# Peripheral.net
KiCad netlist of a schematic drawn in Altium Designer
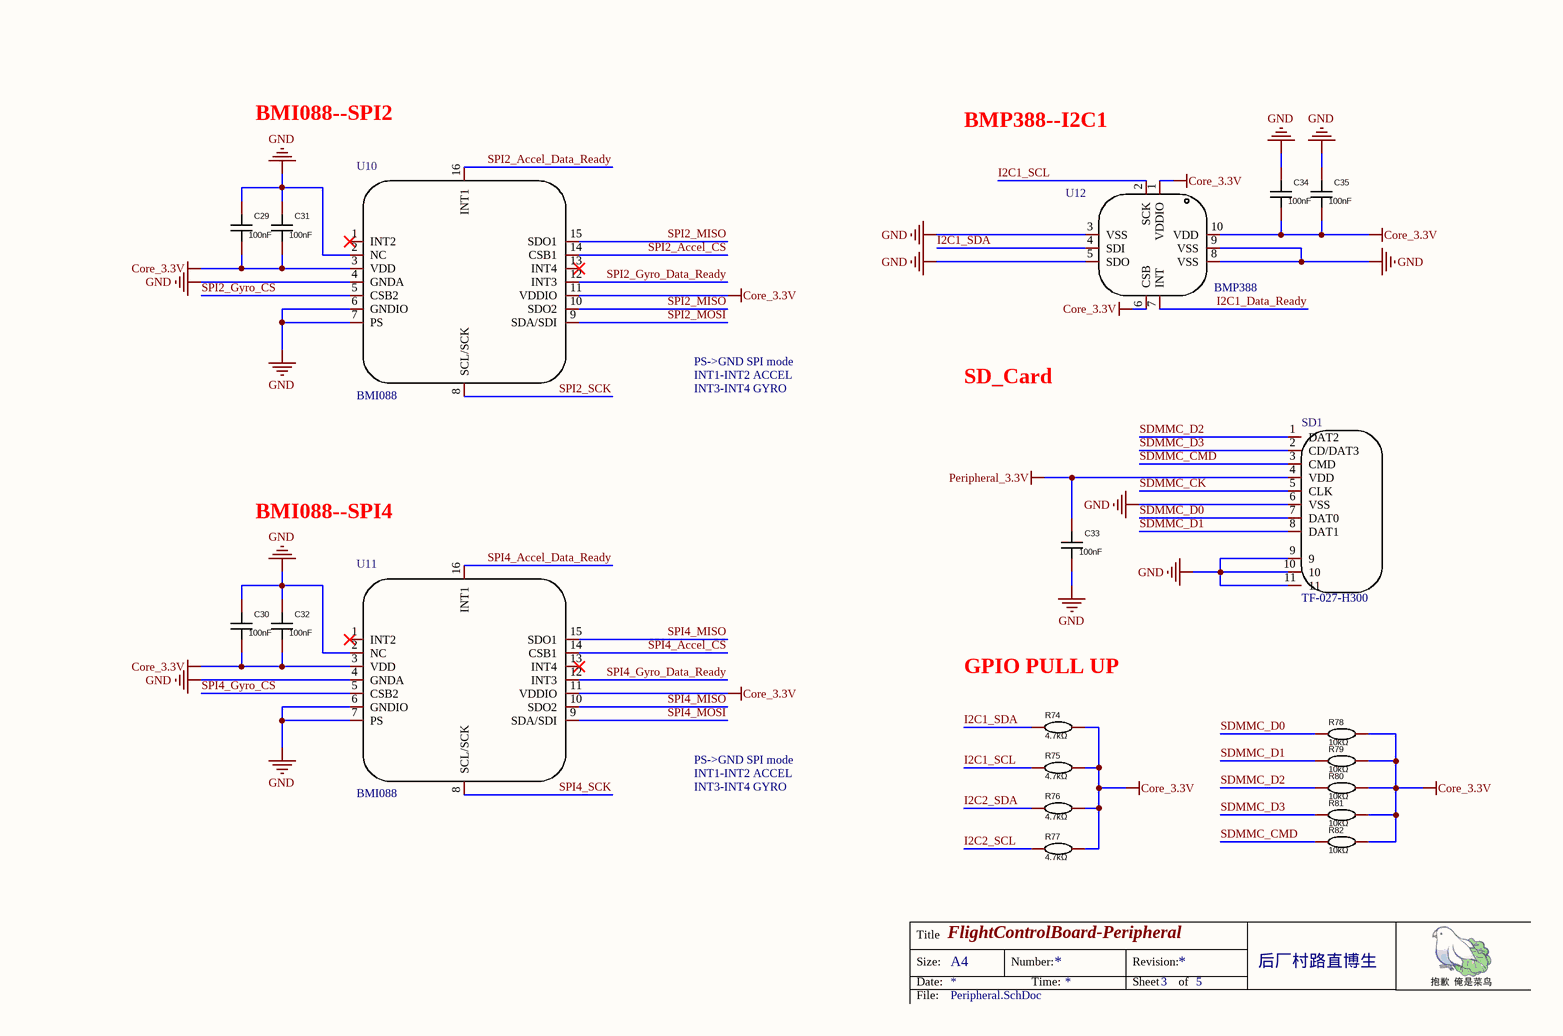
[diagram p0: Peripheral.SchDoc]

(export (version "E")
  (design (tool "Eeschema 10.0.6"))
  (components
    (comp (ref "C29")
      (value "100nF")
      (footprint "C0201")
      (libsource (lib "Capacitor") (part "CC0603KRX7R9BB104"))
    )
    (comp (ref "C30")
      (value "100nF")
      (footprint "C0201")
      (libsource (lib "Capacitor") (part "CC0603KRX7R9BB104"))
    )
    (comp (ref "C31")
      (value "100nF")
      (footprint "C0201")
      (libsource (lib "Capacitor") (part "CC0603KRX7R9BB104"))
    )
    (comp (ref "C32")
      (value "100nF")
      (footprint "C0201")
      (libsource (lib "Capacitor") (part "CC0603KRX7R9BB104"))
    )
    (comp (ref "C33")
      (value "100nF")
      (footprint "C0201")
      (libsource (lib "Capacitor") (part "CC0603KRX7R9BB104"))
    )
    (comp (ref "C34")
      (value "100nF")
      (footprint "C0201")
      (libsource (lib "Capacitor") (part "CC0603KRX7R9BB104"))
    )
    (comp (ref "C35")
      (value "100nF")
      (footprint "C0201")
      (libsource (lib "Capacitor") (part "CC0603KRX7R9BB104"))
    )
    (comp (ref "R74")
      (value "4.7kΩ")
      (footprint "R0201")
      (libsource (lib "Resistor") (part "0603WAF1002T5E"))
    )
    (comp (ref "R75")
      (value "4.7kΩ")
      (footprint "R0201")
      (libsource (lib "Resistor") (part "0603WAF1002T5E"))
    )
    (comp (ref "R76")
      (value "4.7kΩ")
      (footprint "R0201")
      (libsource (lib "Resistor") (part "0603WAF1002T5E"))
    )
    (comp (ref "R77")
      (value "4.7kΩ")
      (footprint "R0201")
      (libsource (lib "Resistor") (part "0603WAF1002T5E"))
    )
    (comp (ref "R78") (value "10kΩ") (footprint "R0201") (libsource (lib "Resistor") (part "0603WAF1002T5E")))
    (comp (ref "R79") (value "10kΩ") (footprint "R0201") (libsource (lib "Resistor") (part "0603WAF1002T5E")))
    (comp (ref "R80") (value "10kΩ") (footprint "R0201") (libsource (lib "Resistor") (part "0603WAF1002T5E")))
    (comp (ref "R81") (value "10kΩ") (footprint "R0201") (libsource (lib "Resistor") (part "0603WAF1002T5E")))
    (comp (ref "R82") (value "10kΩ") (footprint "R0201") (libsource (lib "Resistor") (part "0603WAF1002T5E")))
    (comp (ref "SD1")
      (value "TF-027-H300")
      (footprint "TF-SMD_HYCW104-TF08-375B")
      (fields (field (name "MANUFACTURER") "HANBO(汉博)"))
      (libsource (lib "SD-Card") (part "TF-027-H300"))
    )
    (comp (ref "U10")
      (value "BMI088")
      (footprint "LGA-16_L4.5-W3.0-P0.50-BL")
      (fields (field (name "MANUFACTURER") "Bosch(博世)"))
      (libsource (lib "IMU") (part "BMI088"))
    )
    (comp (ref "U11")
      (value "BMI088")
      (footprint "LGA-16_L4.5-W3.0-P0.50-BL")
      (fields (field (name "MANUFACTURER") "Bosch(博世)"))
      (libsource (lib "IMU") (part "BMI088"))
    )
    (comp (ref "U12")
      (value "BMP388")
      (footprint "LGA-10")
      (fields (field (name "MANUFACTURER") "Bosch(博世)"))
      (libsource (lib "Barometer") (part "BMP388"))
    )
  )
  (nets
    (net (code "1") (name "/I2C1_Data_Ready") (class "Default")
      (node (ref "U12") (pin "7") (pinfunction "INT_7") (pintype "passive"))
    )
    (net (code "2") (name "/I2C1_SCL") (class "Default")
      (node (ref "R75") (pin "1") (pinfunction "1_1") (pintype "passive"))
      (node (ref "U12") (pin "2") (pinfunction "SCK_2") (pintype "passive"))
    )
    (net (code "3") (name "/I2C1_SDA") (class "Default")
      (node (ref "R74") (pin "1") (pinfunction "1_1") (pintype "passive"))
      (node (ref "U12") (pin "4") (pinfunction "SDI_4") (pintype "passive"))
    )
    (net (code "4") (name "/I2C2_SCL") (class "Default")
      (node (ref "R77") (pin "1") (pinfunction "1_1") (pintype "passive"))
    )
    (net (code "5") (name "/I2C2_SDA") (class "Default")
      (node (ref "R76") (pin "1") (pinfunction "1_1") (pintype "passive"))
    )
    (net (code "6") (name "/SDMMC_CK") (class "Default")
      (node (ref "SD1") (pin "5") (pinfunction "CLK_5") (pintype "passive"))
    )
    (net (code "7") (name "/SDMMC_CMD") (class "Default")
      (node (ref "R82") (pin "1") (pinfunction "1_1") (pintype "passive"))
      (node (ref "SD1") (pin "3") (pinfunction "CMD_3") (pintype "passive"))
    )
    (net (code "8") (name "/SDMMC_D0") (class "Default")
      (node (ref "R78") (pin "1") (pinfunction "1_1") (pintype "passive"))
      (node (ref "SD1") (pin "7") (pinfunction "DAT0_7") (pintype "passive"))
    )
    (net (code "9") (name "/SDMMC_D1") (class "Default")
      (node (ref "R79") (pin "1") (pinfunction "1_1") (pintype "passive"))
      (node (ref "SD1") (pin "8") (pinfunction "DAT1_8") (pintype "passive"))
    )
    (net (code "10") (name "/SDMMC_D2") (class "Default")
      (node (ref "R80") (pin "1") (pinfunction "1_1") (pintype "passive"))
      (node (ref "SD1") (pin "1") (pinfunction "DAT2_1") (pintype "passive"))
    )
    (net (code "11") (name "/SDMMC_D3") (class "Default")
      (node (ref "R81") (pin "1") (pinfunction "1_1") (pintype "passive"))
      (node (ref "SD1") (pin "2") (pinfunction "CD/DAT3_2") (pintype "passive"))
    )
    (net (code "12") (name "/SPI2_Accel_CS") (class "Default")
      (node (ref "U10") (pin "14") (pinfunction "CSB1_14") (pintype "passive"))
    )
    (net (code "13") (name "/SPI2_Accel_Data_Ready") (class "Default")
      (node (ref "U10") (pin "16") (pinfunction "INT1_16") (pintype "passive"))
    )
    (net (code "14") (name "/SPI2_Gyro_CS") (class "Default")
      (node (ref "U10") (pin "5") (pinfunction "CSB2_5") (pintype "passive"))
    )
    (net (code "15") (name "/SPI2_Gyro_Data_Ready") (class "Default")
      (node (ref "U10") (pin "12") (pinfunction "INT3_12") (pintype "passive"))
    )
    (net (code "16") (name "/SPI2_MISO") (class "Default")
      (node (ref "U10") (pin "10") (pinfunction "SDO2_10") (pintype "passive"))
      (node (ref "U10") (pin "15") (pinfunction "SDO1_15") (pintype "passive"))
    )
    (net (code "17") (name "/SPI2_MOSI") (class "Default")
      (node (ref "U10") (pin "9") (pinfunction "SDA/SDI_9") (pintype "passive"))
    )
    (net (code "18") (name "/SPI2_SCK") (class "Default")
      (node (ref "U10") (pin "8") (pinfunction "SCL/SCK_8") (pintype "passive"))
    )
    (net (code "19") (name "/SPI4_Accel_CS") (class "Default")
      (node (ref "U11") (pin "14") (pinfunction "CSB1_14") (pintype "passive"))
    )
    (net (code "20") (name "/SPI4_Accel_Data_Ready") (class "Default")
      (node (ref "U11") (pin "16") (pinfunction "INT1_16") (pintype "passive"))
    )
    (net (code "21") (name "/SPI4_Gyro_CS") (class "Default")
      (node (ref "U11") (pin "5") (pinfunction "CSB2_5") (pintype "passive"))
    )
    (net (code "22") (name "/SPI4_Gyro_Data_Ready") (class "Default")
      (node (ref "U11") (pin "12") (pinfunction "INT3_12") (pintype "passive"))
    )
    (net (code "23") (name "/SPI4_MISO") (class "Default")
      (node (ref "U11") (pin "10") (pinfunction "SDO2_10") (pintype "passive"))
      (node (ref "U11") (pin "15") (pinfunction "SDO1_15") (pintype "passive"))
    )
    (net (code "24") (name "/SPI4_MOSI") (class "Default")
      (node (ref "U11") (pin "9") (pinfunction "SDA/SDI_9") (pintype "passive"))
    )
    (net (code "25") (name "/SPI4_SCK") (class "Default")
      (node (ref "U11") (pin "8") (pinfunction "SCL/SCK_8") (pintype "passive"))
    )
    (net (code "26") (name "Core_3.3V") (class "Default")
      (node (ref "C29") (pin "1") (pinfunction "1_1") (pintype "passive"))
      (node (ref "C30") (pin "1") (pinfunction "1_1") (pintype "passive"))
      (node (ref "C31") (pin "1") (pinfunction "1_1") (pintype "passive"))
      (node (ref "C32") (pin "1") (pinfunction "1_1") (pintype "passive"))
      (node (ref "C34") (pin "1") (pinfunction "1_1") (pintype "passive"))
      (node (ref "C35") (pin "1") (pinfunction "1_1") (pintype "passive"))
      (node (ref "R74") (pin "2") (pinfunction "2_2") (pintype "passive"))
      (node (ref "R75") (pin "2") (pinfunction "2_2") (pintype "passive"))
      (node (ref "R76") (pin "2") (pinfunction "2_2") (pintype "passive"))
      (node (ref "R77") (pin "2") (pinfunction "2_2") (pintype "passive"))
      (node (ref "R78") (pin "2") (pinfunction "2_2") (pintype "passive"))
      (node (ref "R79") (pin "2") (pinfunction "2_2") (pintype "passive"))
      (node (ref "R80") (pin "2") (pinfunction "2_2") (pintype "passive"))
      (node (ref "R81") (pin "2") (pinfunction "2_2") (pintype "passive"))
      (node (ref "R82") (pin "2") (pinfunction "2_2") (pintype "passive"))
      (node (ref "U10") (pin "11") (pinfunction "VDDIO_11") (pintype "passive"))
      (node (ref "U10") (pin "3") (pinfunction "VDD_3") (pintype "passive"))
      (node (ref "U11") (pin "11") (pinfunction "VDDIO_11") (pintype "passive"))
      (node (ref "U11") (pin "3") (pinfunction "VDD_3") (pintype "passive"))
      (node (ref "U12") (pin "1") (pinfunction "VDDIO_1") (pintype "passive"))
      (node (ref "U12") (pin "10") (pinfunction "VDD_10") (pintype "passive"))
      (node (ref "U12") (pin "6") (pinfunction "CSB_6") (pintype "passive"))
    )
    (net (code "27") (name "GND") (class "Default")
      (node (ref "C29") (pin "2") (pinfunction "2_2") (pintype "passive"))
      (node (ref "C30") (pin "2") (pinfunction "2_2") (pintype "passive"))
      (node (ref "C31") (pin "2") (pinfunction "2_2") (pintype "passive"))
      (node (ref "C32") (pin "2") (pinfunction "2_2") (pintype "passive"))
      (node (ref "C33") (pin "1") (pinfunction "1_1") (pintype "passive"))
      (node (ref "C34") (pin "2") (pinfunction "2_2") (pintype "passive"))
      (node (ref "C35") (pin "2") (pinfunction "2_2") (pintype "passive"))
      (node (ref "SD1") (pin "10") (pinfunction "10_10") (pintype "passive"))
      (node (ref "SD1") (pin "11") (pinfunction "11_11") (pintype "passive"))
      (node (ref "SD1") (pin "6") (pinfunction "VSS_6") (pintype "passive"))
      (node (ref "SD1") (pin "9") (pinfunction "9_9") (pintype "passive"))
      (node (ref "U10") (pin "2") (pinfunction "NC_2") (pintype "passive"))
      (node (ref "U10") (pin "4") (pinfunction "GNDA_4") (pintype "passive"))
      (node (ref "U10") (pin "6") (pinfunction "GNDIO_6") (pintype "passive"))
      (node (ref "U10") (pin "7") (pinfunction "PS_7") (pintype "passive"))
      (node (ref "U11") (pin "2") (pinfunction "NC_2") (pintype "passive"))
      (node (ref "U11") (pin "4") (pinfunction "GNDA_4") (pintype "passive"))
      (node (ref "U11") (pin "6") (pinfunction "GNDIO_6") (pintype "passive"))
      (node (ref "U11") (pin "7") (pinfunction "PS_7") (pintype "passive"))
      (node (ref "U12") (pin "3") (pinfunction "VSS_3") (pintype "passive"))
      (node (ref "U12") (pin "5") (pinfunction "SDO_5") (pintype "passive"))
      (node (ref "U12") (pin "8") (pinfunction "VSS_8") (pintype "passive"))
      (node (ref "U12") (pin "9") (pinfunction "VSS_9") (pintype "passive"))
    )
    (net (code "28") (name "Peripheral_3.3V") (class "Default")
      (node (ref "C33") (pin "2") (pinfunction "2_2") (pintype "passive"))
      (node (ref "SD1") (pin "4") (pinfunction "VDD_4") (pintype "passive"))
    )
    (net (code "29") (name "unconnected-(U10-INT2-Pad1)") (class "Default")
      (node (ref "U10") (pin "1") (pinfunction "INT2_1") (pintype "passive+no_connect"))
    )
    (net (code "30") (name "unconnected-(U10-INT4-Pad13)") (class "Default")
      (node (ref "U10") (pin "13") (pinfunction "INT4_13") (pintype "passive+no_connect"))
    )
    (net (code "31") (name "unconnected-(U11-INT2-Pad1)") (class "Default")
      (node (ref "U11") (pin "1") (pinfunction "INT2_1") (pintype "passive+no_connect"))
    )
    (net (code "32") (name "unconnected-(U11-INT4-Pad13)") (class "Default")
      (node (ref "U11") (pin "13") (pinfunction "INT4_13") (pintype "passive+no_connect"))
    )
  )
)
